# whoop-v0_11td.net
KiCad netlist of a schematic drawn in EAGLE
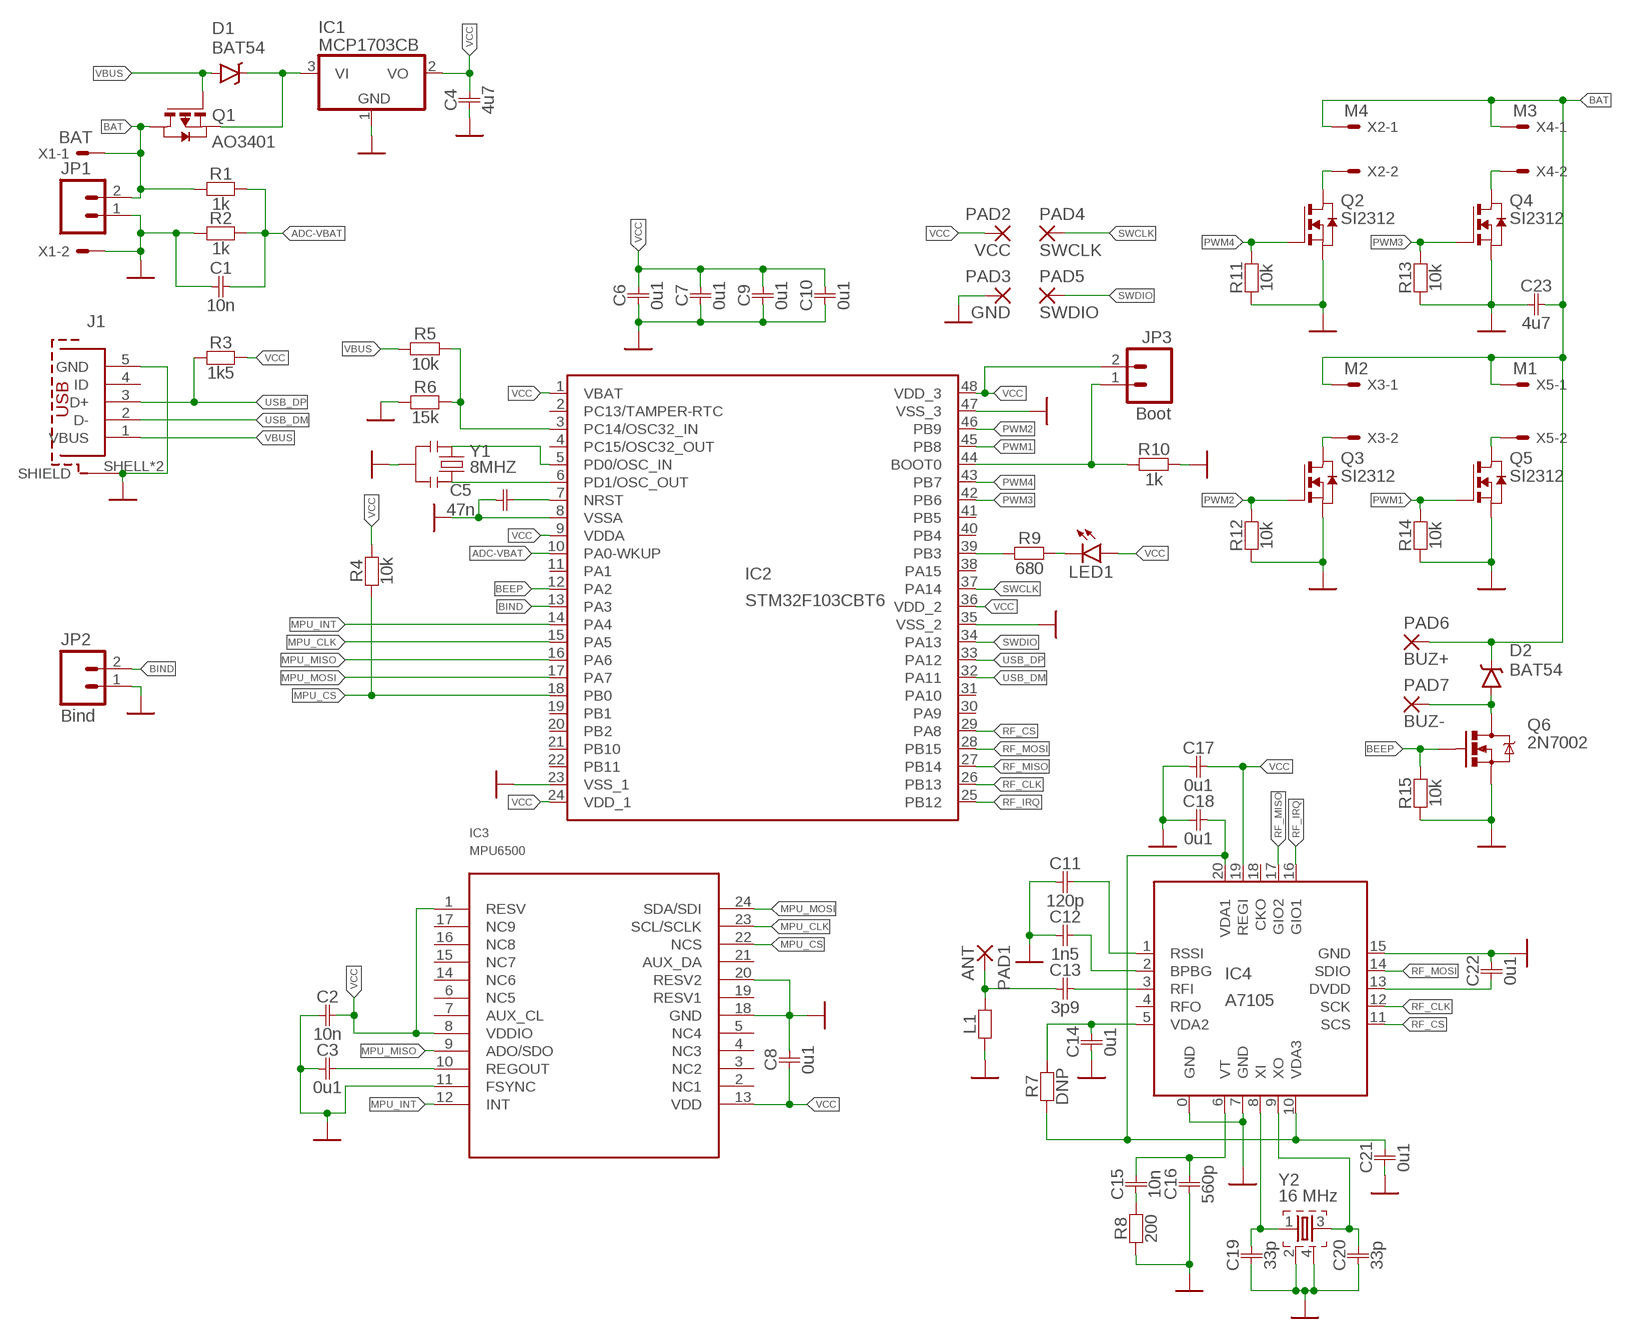
[diagram p0: schematic, sheet 1]

(export (version "E")
  (design (tool "Eeschema 10.0.6"))
  (components
    (comp (ref "C1")
      (value "10n")
      (footprint "eagle-import:0402")
      (libsource (lib "eagle-import") (part "C0402"))
    )
    (comp (ref "C2")
      (value "10n")
      (footprint "eagle-import:0402")
      (libsource (lib "eagle-import") (part "C0402"))
    )
    (comp (ref "C3")
      (value "0u1")
      (footprint "eagle-import:0402")
      (libsource (lib "eagle-import") (part "C0402"))
    )
    (comp (ref "C4")
      (value "4u7")
      (footprint "eagle-import:0805")
      (libsource (lib "eagle-import") (part "C0805"))
    )
    (comp (ref "C5")
      (value "47n")
      (footprint "eagle-import:0402")
      (libsource (lib "eagle-import") (part "C0402"))
    )
    (comp (ref "C6")
      (value "0u1")
      (footprint "eagle-import:0402")
      (libsource (lib "eagle-import") (part "C0402"))
    )
    (comp (ref "C7")
      (value "0u1")
      (footprint "eagle-import:0402")
      (libsource (lib "eagle-import") (part "C0402"))
    )
    (comp (ref "C8")
      (value "0u1")
      (footprint "eagle-import:0402")
      (libsource (lib "eagle-import") (part "C0402"))
    )
    (comp (ref "C9")
      (value "0u1")
      (footprint "eagle-import:0402")
      (libsource (lib "eagle-import") (part "C0402"))
    )
    (comp (ref "C10")
      (value "0u1")
      (footprint "eagle-import:0402")
      (libsource (lib "eagle-import") (part "C0402"))
    )
    (comp (ref "C11")
      (value "120p")
      (footprint "eagle-import:0402")
      (libsource (lib "eagle-import") (part "C0402"))
    )
    (comp (ref "C12")
      (value "1n5")
      (footprint "eagle-import:0402")
      (libsource (lib "eagle-import") (part "C0402"))
    )
    (comp (ref "C13")
      (value "3p9")
      (footprint "eagle-import:0402")
      (libsource (lib "eagle-import") (part "C0402"))
    )
    (comp (ref "C14")
      (value "0u1")
      (footprint "eagle-import:0402")
      (libsource (lib "eagle-import") (part "C0402"))
    )
    (comp (ref "C15")
      (value "10n")
      (footprint "eagle-import:0402")
      (libsource (lib "eagle-import") (part "C0402"))
    )
    (comp (ref "C16")
      (value "560p")
      (footprint "eagle-import:0402")
      (libsource (lib "eagle-import") (part "C0402"))
    )
    (comp (ref "C17")
      (value "0u1")
      (footprint "eagle-import:0402")
      (libsource (lib "eagle-import") (part "C0402"))
    )
    (comp (ref "C18")
      (value "0u1")
      (footprint "eagle-import:0402")
      (libsource (lib "eagle-import") (part "C0402"))
    )
    (comp (ref "C19")
      (value "33p")
      (footprint "eagle-import:0402")
      (libsource (lib "eagle-import") (part "C0402"))
    )
    (comp (ref "C20")
      (value "33p")
      (footprint "eagle-import:0402")
      (libsource (lib "eagle-import") (part "C0402"))
    )
    (comp (ref "C21")
      (value "0u1")
      (footprint "eagle-import:0402")
      (libsource (lib "eagle-import") (part "C0402"))
    )
    (comp (ref "C22")
      (value "0u1")
      (footprint "eagle-import:0402")
      (libsource (lib "eagle-import") (part "C0402"))
    )
    (comp (ref "C23")
      (value "4u7")
      (footprint "eagle-import:0805")
      (libsource (lib "eagle-import") (part "C0805"))
    )
    (comp (ref "D1")
      (value "BAT54")
      (footprint "eagle-import:SOD-323")
      (libsource (lib "eagle-import") (part "BAT20JFILM"))
    )
    (comp (ref "D2")
      (value "BAT54")
      (footprint "eagle-import:SOD-323")
      (libsource (lib "eagle-import") (part "BAT20JFILM"))
    )
    (comp (ref "IC1")
      (value "MCP1703CB")
      (footprint "eagle-import:SOT23")
      (libsource (lib "eagle-import") (part "MCP1703CB"))
    )
    (comp (ref "IC2")
      (value "STM32F103CBT6")
      (footprint "eagle-import:LQFP48")
      (libsource (lib "eagle-import") (part "STM32F103C8"))
    )
    (comp (ref "IC3")
      (value "MPU6500")
      (footprint "eagle-import:LEAD-QFN24")
      (libsource (lib "eagle-import") (part "MPU-9250"))
    )
    (comp (ref "IC4")
      (value "A7105")
      (footprint "eagle-import:QFN20")
      (libsource (lib "eagle-import") (part "A7105"))
    )
    (comp (ref "J1")
      (value "614105150721")
      (footprint "eagle-import:614105150721")
      (libsource (lib "eagle-import") (part "614105150721"))
    )
    (comp (ref "JP1")
      (value "M022MM")
      (footprint "eagle-import:1X02_2MM")
      (libsource (lib "eagle-import") (part "M022MM"))
    )
    (comp (ref "JP2")
      (value "Bind")
      (footprint "eagle-import:1X02_1.27MM")
      (libsource (lib "eagle-import") (part "M021.27MM"))
    )
    (comp (ref "JP3")
      (value "Boot")
      (footprint "eagle-import:1X02_1.27MM")
      (libsource (lib "eagle-import") (part "M021.27MM"))
    )
    (comp (ref "L1")
      (value "R0402")
      (footprint "eagle-import:0402")
      (libsource (lib "eagle-import") (part "R0402"))
    )
    (comp (ref "LED1")
      (value "LED-RED0603")
      (footprint "eagle-import:LED-0603")
      (libsource (lib "eagle-import") (part "LED-RED0603"))
    )
    (comp (ref "PAD1")
      (value "ANT")
      (footprint "eagle-import:1,6_0,8")
      (libsource (lib "eagle-import") (part "1,6/0,8"))
    )
    (comp (ref "PAD2")
      (value "VCC")
      (footprint "eagle-import:SMD1,27-2,54")
      (libsource (lib "eagle-import") (part "SMD2"))
    )
    (comp (ref "PAD3")
      (value "GND")
      (footprint "eagle-import:SMD1,27-2,54")
      (libsource (lib "eagle-import") (part "SMD2"))
    )
    (comp (ref "PAD4")
      (value "SWCLK")
      (footprint "eagle-import:SMD1,27-2,54")
      (libsource (lib "eagle-import") (part "SMD2"))
    )
    (comp (ref "PAD5")
      (value "SWDIO")
      (footprint "eagle-import:SMD1,27-2,54")
      (libsource (lib "eagle-import") (part "SMD2"))
    )
    (comp (ref "PAD6")
      (value "BUZ+")
      (footprint "eagle-import:SMD1,27-2,54")
      (libsource (lib "eagle-import") (part "SMD2"))
    )
    (comp (ref "PAD7")
      (value "BUZ-")
      (footprint "eagle-import:SMD1,27-2,54")
      (libsource (lib "eagle-import") (part "SMD2"))
    )
    (comp (ref "Q1")
      (value "AO3401")
      (footprint "eagle-import:SOT-23")
      (libsource (lib "eagle-import") (part "PMOSSOT23"))
    )
    (comp (ref "Q2")
      (value "SI2312")
      (footprint "eagle-import:SOT-23")
      (libsource (lib "eagle-import") (part "NMOSSOT23"))
    )
    (comp (ref "Q3")
      (value "SI2312")
      (footprint "eagle-import:SOT-23")
      (libsource (lib "eagle-import") (part "NMOSSOT23"))
    )
    (comp (ref "Q4")
      (value "SI2312")
      (footprint "eagle-import:SOT-23")
      (libsource (lib "eagle-import") (part "NMOSSOT23"))
    )
    (comp (ref "Q5")
      (value "SI2312")
      (footprint "eagle-import:SOT-23")
      (libsource (lib "eagle-import") (part "NMOSSOT23"))
    )
    (comp (ref "Q6")
      (value "2N7002")
      (footprint "eagle-import:SOT323")
      (libsource (lib "eagle-import") (part "MOSFET-NCHANNEL2N7002PW"))
    )
    (comp (ref "R1")
      (value "1k")
      (footprint "eagle-import:0402")
      (libsource (lib "eagle-import") (part "R0402"))
    )
    (comp (ref "R2")
      (value "1k")
      (footprint "eagle-import:0402")
      (libsource (lib "eagle-import") (part "R0402"))
    )
    (comp (ref "R3")
      (value "1k5")
      (footprint "eagle-import:0402")
      (libsource (lib "eagle-import") (part "R0402"))
    )
    (comp (ref "R4")
      (value "10k")
      (footprint "eagle-import:0402")
      (libsource (lib "eagle-import") (part "R0402"))
    )
    (comp (ref "R5")
      (value "10k")
      (footprint "eagle-import:0402")
      (libsource (lib "eagle-import") (part "R0402"))
    )
    (comp (ref "R6")
      (value "15k")
      (footprint "eagle-import:0402")
      (libsource (lib "eagle-import") (part "R0402"))
    )
    (comp (ref "R7")
      (value "DNP")
      (footprint "eagle-import:0402")
      (libsource (lib "eagle-import") (part "R0402"))
    )
    (comp (ref "R8")
      (value "200")
      (footprint "eagle-import:0402")
      (libsource (lib "eagle-import") (part "R0402"))
    )
    (comp (ref "R9")
      (value "680")
      (footprint "eagle-import:0402")
      (libsource (lib "eagle-import") (part "R0402"))
    )
    (comp (ref "R10")
      (value "1k")
      (footprint "eagle-import:0402")
      (libsource (lib "eagle-import") (part "R0402"))
    )
    (comp (ref "R11")
      (value "10k")
      (footprint "eagle-import:0402")
      (libsource (lib "eagle-import") (part "R0402"))
    )
    (comp (ref "R12")
      (value "10k")
      (footprint "eagle-import:0402")
      (libsource (lib "eagle-import") (part "R0402"))
    )
    (comp (ref "R13")
      (value "10k")
      (footprint "eagle-import:0402")
      (libsource (lib "eagle-import") (part "R0402"))
    )
    (comp (ref "R14")
      (value "10k")
      (footprint "eagle-import:0402")
      (libsource (lib "eagle-import") (part "R0402"))
    )
    (comp (ref "R15")
      (value "10k")
      (footprint "eagle-import:0402")
      (libsource (lib "eagle-import") (part "R0402"))
    )
    (comp (ref "X1")
      (value "BAT")
      (footprint "eagle-import:53047-02")
      (fields (field (name "MF") "MOLEX") (field (name "MPN") "53047-0210"))
      (libsource (lib "eagle-import") (part "53?-02047"))
    )
    (comp (ref "X2")
      (value "M4")
      (footprint "eagle-import:53047-02")
      (fields (field (name "MF") "MOLEX") (field (name "MPN") "53047-0210"))
      (libsource (lib "eagle-import") (part "53?-02047"))
    )
    (comp (ref "X3")
      (value "M2")
      (footprint "eagle-import:53047-02")
      (fields (field (name "MF") "MOLEX") (field (name "MPN") "53047-0210"))
      (libsource (lib "eagle-import") (part "53?-02047"))
    )
    (comp (ref "X4")
      (value "M3")
      (footprint "eagle-import:53047-02")
      (fields (field (name "MF") "MOLEX") (field (name "MPN") "53047-0210"))
      (libsource (lib "eagle-import") (part "53?-02047"))
    )
    (comp (ref "X5")
      (value "M1")
      (footprint "eagle-import:53047-02")
      (fields (field (name "MF") "MOLEX") (field (name "MPN") "53047-0210"))
      (libsource (lib "eagle-import") (part "53?-02047"))
    )
    (comp (ref "Y1")
      (value "8MHZ")
      (footprint "eagle-import:RESONATOR-SMD")
      (libsource (lib "eagle-import") (part "RESONATOR8MHZ"))
    )
    (comp (ref "Y2")
      (value "16 MHz")
      (footprint "eagle-import:FA-20H")
      (libsource (lib "eagle-import") (part "FA-3225"))
    )
  )
  (nets
    (net (code "1") (name "ADC-VBAT") (class "Default")
      (node (ref "C1") (pin "P$2") (pinfunction "P$2_P$2") (pintype "passive"))
      (node (ref "IC2") (pin "10") (pinfunction "PA0-WKUP_10") (pintype "bidirectional"))
      (node (ref "R1") (pin "P$1") (pinfunction "P$1_P$1") (pintype "passive"))
      (node (ref "R2") (pin "P$1") (pinfunction "P$1_P$1") (pintype "passive"))
    )
    (net (code "2") (name "BAT") (class "Default")
      (node (ref "C23") (pin "P$2") (pinfunction "P$2_P$2") (pintype "passive"))
      (node (ref "D2") (pin "C") (pinfunction "C_C") (pintype "passive"))
      (node (ref "JP1") (pin "2") (pinfunction "2_2") (pintype "passive"))
      (node (ref "PAD6") (pin "1") (pinfunction "P_1") (pintype "passive"))
      (node (ref "Q1") (pin "1") (pinfunction "D_1") (pintype "passive"))
      (node (ref "R1") (pin "P$2") (pinfunction "P$2_P$2") (pintype "passive"))
      (node (ref "X1") (pin "1") (pinfunction "S_1") (pintype "passive"))
      (node (ref "X2") (pin "1") (pinfunction "S_1") (pintype "passive"))
      (node (ref "X3") (pin "1") (pinfunction "S_1") (pintype "passive"))
      (node (ref "X4") (pin "1") (pinfunction "S_1") (pintype "passive"))
      (node (ref "X5") (pin "1") (pinfunction "S_1") (pintype "passive"))
    )
    (net (code "3") (name "BEEP") (class "Default")
      (node (ref "IC2") (pin "12") (pinfunction "PA2_12") (pintype "bidirectional"))
      (node (ref "Q6") (pin "1") (pinfunction "G_1") (pintype "passive"))
      (node (ref "R15") (pin "P$2") (pinfunction "P$2_P$2") (pintype "passive"))
    )
    (net (code "4") (name "BIND") (class "Default")
      (node (ref "IC2") (pin "13") (pinfunction "PA3_13") (pintype "bidirectional"))
      (node (ref "JP2") (pin "2") (pinfunction "2_2") (pintype "passive"))
    )
    (net (code "5") (name "GND") (class "Default")
      (node (ref "C1") (pin "P$1") (pinfunction "P$1_P$1") (pintype "passive"))
      (node (ref "C10") (pin "P$1") (pinfunction "P$1_P$1") (pintype "passive"))
      (node (ref "C11") (pin "P$1") (pinfunction "P$1_P$1") (pintype "passive"))
      (node (ref "C12") (pin "P$1") (pinfunction "P$1_P$1") (pintype "passive"))
      (node (ref "C14") (pin "P$1") (pinfunction "P$1_P$1") (pintype "passive"))
      (node (ref "C16") (pin "P$1") (pinfunction "P$1_P$1") (pintype "passive"))
      (node (ref "C17") (pin "P$1") (pinfunction "P$1_P$1") (pintype "passive"))
      (node (ref "C18") (pin "P$1") (pinfunction "P$1_P$1") (pintype "passive"))
      (node (ref "C19") (pin "P$1") (pinfunction "P$1_P$1") (pintype "passive"))
      (node (ref "C2") (pin "P$1") (pinfunction "P$1_P$1") (pintype "passive"))
      (node (ref "C20") (pin "P$1") (pinfunction "P$1_P$1") (pintype "passive"))
      (node (ref "C21") (pin "P$1") (pinfunction "P$1_P$1") (pintype "passive"))
      (node (ref "C22") (pin "P$2") (pinfunction "P$2_P$2") (pintype "passive"))
      (node (ref "C23") (pin "P$1") (pinfunction "P$1_P$1") (pintype "passive"))
      (node (ref "C3") (pin "P$1") (pinfunction "P$1_P$1") (pintype "passive"))
      (node (ref "C4") (pin "P$1") (pinfunction "P$1_P$1") (pintype "passive"))
      (node (ref "C5") (pin "P$1") (pinfunction "P$1_P$1") (pintype "passive"))
      (node (ref "C6") (pin "P$1") (pinfunction "P$1_P$1") (pintype "passive"))
      (node (ref "C7") (pin "P$1") (pinfunction "P$1_P$1") (pintype "passive"))
      (node (ref "C8") (pin "P$2") (pinfunction "P$2_P$2") (pintype "passive"))
      (node (ref "C9") (pin "P$1") (pinfunction "P$1_P$1") (pintype "passive"))
      (node (ref "IC1") (pin "1") (pinfunction "GND_1") (pintype "passive"))
      (node (ref "IC2") (pin "23") (pinfunction "VSS_1_23") (pintype "power_in"))
      (node (ref "IC2") (pin "35") (pinfunction "VSS_2_35") (pintype "power_in"))
      (node (ref "IC2") (pin "47") (pinfunction "VSS_3_47") (pintype "power_in"))
      (node (ref "IC2") (pin "8") (pinfunction "VSSA_8") (pintype "power_in"))
      (node (ref "IC3") (pin "11") (pinfunction "FSYNC_11") (pintype "bidirectional"))
      (node (ref "IC3") (pin "18") (pinfunction "GND_18") (pintype "bidirectional"))
      (node (ref "IC3") (pin "20") (pinfunction "RESV2_20") (pintype "bidirectional"))
      (node (ref "IC4") (pin "0") (pinfunction "GND_0") (pintype "power_in"))
      (node (ref "IC4") (pin "15") (pinfunction "GND_15") (pintype "power_in"))
      (node (ref "IC4") (pin "7") (pinfunction "GND_7") (pintype "power_in"))
      (node (ref "J1") (pin "5") (pinfunction "GND_5") (pintype "passive"))
      (node (ref "J1") (pin "SHELL") (pinfunction "SHIELD_SHELL") (pintype "passive"))
      (node (ref "J1") (pin "SHELL1") (pinfunction "SHIELD_SHELL1") (pintype "passive"))
      (node (ref "JP1") (pin "1") (pinfunction "1_1") (pintype "passive"))
      (node (ref "JP2") (pin "1") (pinfunction "1_1") (pintype "passive"))
      (node (ref "L1") (pin "P$1") (pinfunction "P$1_P$1") (pintype "passive"))
      (node (ref "PAD3") (pin "1") (pinfunction "P_1") (pintype "passive"))
      (node (ref "Q2") (pin "2") (pinfunction "S_2") (pintype "passive"))
      (node (ref "Q3") (pin "2") (pinfunction "S_2") (pintype "passive"))
      (node (ref "Q4") (pin "2") (pinfunction "S_2") (pintype "passive"))
      (node (ref "Q5") (pin "2") (pinfunction "S_2") (pintype "passive"))
      (node (ref "Q6") (pin "2") (pinfunction "S_2") (pintype "passive"))
      (node (ref "R10") (pin "P$2") (pinfunction "P$2_P$2") (pintype "passive"))
      (node (ref "R11") (pin "P$1") (pinfunction "P$1_P$1") (pintype "passive"))
      (node (ref "R12") (pin "P$1") (pinfunction "P$1_P$1") (pintype "passive"))
      (node (ref "R13") (pin "P$1") (pinfunction "P$1_P$1") (pintype "passive"))
      (node (ref "R14") (pin "P$1") (pinfunction "P$1_P$1") (pintype "passive"))
      (node (ref "R15") (pin "P$1") (pinfunction "P$1_P$1") (pintype "passive"))
      (node (ref "R2") (pin "P$2") (pinfunction "P$2_P$2") (pintype "passive"))
      (node (ref "R6") (pin "P$2") (pinfunction "P$2_P$2") (pintype "passive"))
      (node (ref "R8") (pin "P$1") (pinfunction "P$1_P$1") (pintype "passive"))
      (node (ref "X1") (pin "2") (pinfunction "S_2") (pintype "passive"))
      (node (ref "Y1") (pin "2") (pinfunction "2_2") (pintype "passive"))
      (node (ref "Y2") (pin "2") (pinfunction "2_2") (pintype "passive"))
      (node (ref "Y2") (pin "4") (pinfunction "4_4") (pintype "passive"))
    )
    (net (code "6") (name "MPU_CLK") (class "Default")
      (node (ref "IC2") (pin "15") (pinfunction "PA5_15") (pintype "bidirectional"))
      (node (ref "IC3") (pin "23") (pinfunction "SCL/SCLK_23") (pintype "bidirectional"))
    )
    (net (code "7") (name "MPU_CS") (class "Default")
      (node (ref "IC2") (pin "18") (pinfunction "PB0_18") (pintype "bidirectional"))
      (node (ref "IC3") (pin "22") (pinfunction "NCS_22") (pintype "bidirectional"))
      (node (ref "R4") (pin "P$1") (pinfunction "P$1_P$1") (pintype "passive"))
    )
    (net (code "8") (name "MPU_INT") (class "Default")
      (node (ref "IC2") (pin "14") (pinfunction "PA4_14") (pintype "bidirectional"))
      (node (ref "IC3") (pin "12") (pinfunction "INT_12") (pintype "bidirectional"))
    )
    (net (code "9") (name "MPU_MISO") (class "Default")
      (node (ref "IC2") (pin "16") (pinfunction "PA6_16") (pintype "bidirectional"))
      (node (ref "IC3") (pin "9") (pinfunction "ADO/SDO_9") (pintype "bidirectional"))
    )
    (net (code "10") (name "MPU_MOSI") (class "Default")
      (node (ref "IC2") (pin "17") (pinfunction "PA7_17") (pintype "bidirectional"))
      (node (ref "IC3") (pin "24") (pinfunction "SDA/SDI_24") (pintype "bidirectional"))
    )
    (net (code "11") (name "Net-(C15-PadP$1)") (class "Default")
      (node (ref "C15") (pin "P$1") (pinfunction "P$1_P$1") (pintype "passive"))
      (node (ref "R8") (pin "P$2") (pinfunction "P$2_P$2") (pintype "passive"))
    )
    (net (code "12") (name "Net-(IC1-VI)") (class "Default")
      (node (ref "D1") (pin "C") (pinfunction "C_C") (pintype "passive"))
      (node (ref "IC1") (pin "3") (pinfunction "VI_3") (pintype "input"))
      (node (ref "Q1") (pin "2") (pinfunction "S_2") (pintype "passive"))
    )
    (net (code "13") (name "Net-(IC2-BOOT0)") (class "Default")
      (node (ref "IC2") (pin "44") (pinfunction "BOOT0_44") (pintype "input"))
      (node (ref "JP3") (pin "1") (pinfunction "1_1") (pintype "passive"))
      (node (ref "R10") (pin "P$1") (pinfunction "P$1_P$1") (pintype "passive"))
    )
    (net (code "14") (name "Net-(IC2-NRST)") (class "Default")
      (node (ref "C5") (pin "P$2") (pinfunction "P$2_P$2") (pintype "passive"))
      (node (ref "IC2") (pin "7") (pinfunction "NRST_7") (pintype "input"))
    )
    (net (code "15") (name "Net-(IC2-PB3)") (class "Default")
      (node (ref "IC2") (pin "39") (pinfunction "PB3_39") (pintype "bidirectional"))
      (node (ref "R9") (pin "P$1") (pinfunction "P$1_P$1") (pintype "passive"))
    )
    (net (code "16") (name "Net-(IC2-PC14{slash}OSC32_IN)") (class "Default")
      (node (ref "IC2") (pin "3") (pinfunction "PC14/OSC32_IN_3") (pintype "bidirectional"))
      (node (ref "R5") (pin "P$2") (pinfunction "P$2_P$2") (pintype "passive"))
      (node (ref "R6") (pin "P$1") (pinfunction "P$1_P$1") (pintype "passive"))
    )
    (net (code "17") (name "Net-(IC2-PD0{slash}OSC_IN)") (class "Default")
      (node (ref "IC2") (pin "5") (pinfunction "PD0/OSC_IN_5") (pintype "bidirectional"))
      (node (ref "Y1") (pin "1") (pinfunction "1_1") (pintype "passive"))
    )
    (net (code "18") (name "Net-(IC2-PD1{slash}OSC_OUT)") (class "Default")
      (node (ref "IC2") (pin "6") (pinfunction "PD1/OSC_OUT_6") (pintype "bidirectional"))
      (node (ref "Y1") (pin "3") (pinfunction "3_3") (pintype "passive"))
    )
    (net (code "19") (name "Net-(IC3-REGOUT)") (class "Default")
      (node (ref "C3") (pin "P$2") (pinfunction "P$2_P$2") (pintype "passive"))
      (node (ref "IC3") (pin "10") (pinfunction "REGOUT_10") (pintype "bidirectional"))
    )
    (net (code "20") (name "Net-(IC4-BPBG)") (class "Default")
      (node (ref "C12") (pin "P$2") (pinfunction "P$2_P$2") (pintype "passive"))
      (node (ref "IC4") (pin "2") (pinfunction "BPBG_2") (pintype "output"))
    )
    (net (code "21") (name "Net-(IC4-DVDD)") (class "Default")
      (node (ref "C22") (pin "P$1") (pinfunction "P$1_P$1") (pintype "passive"))
      (node (ref "IC4") (pin "13") (pinfunction "DVDD_13") (pintype "input"))
    )
    (net (code "22") (name "Net-(IC4-RFI)") (class "Default")
      (node (ref "C13") (pin "P$2") (pinfunction "P$2_P$2") (pintype "passive"))
      (node (ref "IC4") (pin "3") (pinfunction "RFI_3") (pintype "input"))
    )
    (net (code "23") (name "Net-(IC4-RSSI)") (class "Default")
      (node (ref "C11") (pin "P$2") (pinfunction "P$2_P$2") (pintype "passive"))
      (node (ref "IC4") (pin "1") (pinfunction "RSSI_1") (pintype "output"))
    )
    (net (code "24") (name "Net-(IC4-VDA1)") (class "Default")
      (node (ref "C18") (pin "P$2") (pinfunction "P$2_P$2") (pintype "passive"))
      (node (ref "C21") (pin "P$2") (pinfunction "P$2_P$2") (pintype "passive"))
      (node (ref "IC4") (pin "10") (pinfunction "VDA3_10") (pintype "input"))
      (node (ref "IC4") (pin "20") (pinfunction "VDA1_20") (pintype "bidirectional"))
      (node (ref "R7") (pin "P$1") (pinfunction "P$1_P$1") (pintype "passive"))
    )
    (net (code "25") (name "Net-(IC4-VDA2)") (class "Default")
      (node (ref "C14") (pin "P$2") (pinfunction "P$2_P$2") (pintype "passive"))
      (node (ref "IC4") (pin "5") (pinfunction "VDA2_5") (pintype "bidirectional"))
      (node (ref "R7") (pin "P$2") (pinfunction "P$2_P$2") (pintype "passive"))
    )
    (net (code "26") (name "Net-(IC4-VT)") (class "Default")
      (node (ref "C15") (pin "P$2") (pinfunction "P$2_P$2") (pintype "passive"))
      (node (ref "C16") (pin "P$2") (pinfunction "P$2_P$2") (pintype "passive"))
      (node (ref "IC4") (pin "6") (pinfunction "VT_6") (pintype "input"))
    )
    (net (code "27") (name "Net-(IC4-XI)") (class "Default")
      (node (ref "C19") (pin "P$2") (pinfunction "P$2_P$2") (pintype "passive"))
      (node (ref "IC4") (pin "8") (pinfunction "XI_8") (pintype "input"))
      (node (ref "Y2") (pin "1") (pinfunction "1_1") (pintype "passive"))
    )
    (net (code "28") (name "Net-(IC4-XO)") (class "Default")
      (node (ref "C20") (pin "P$2") (pinfunction "P$2_P$2") (pintype "passive"))
      (node (ref "IC4") (pin "9") (pinfunction "XO_9") (pintype "output"))
      (node (ref "Y2") (pin "3") (pinfunction "3_3") (pintype "passive"))
    )
    (net (code "29") (name "Net-(LED1-PadC)") (class "Default")
      (node (ref "LED1") (pin "C") (pinfunction "C_C") (pintype "passive"))
      (node (ref "R9") (pin "P$2") (pinfunction "P$2_P$2") (pintype "passive"))
    )
    (net (code "30") (name "Net-(PAD1-P)") (class "Default")
      (node (ref "C13") (pin "P$1") (pinfunction "P$1_P$1") (pintype "passive"))
      (node (ref "L1") (pin "P$2") (pinfunction "P$2_P$2") (pintype "passive"))
      (node (ref "PAD1") (pin "1") (pinfunction "P_1") (pintype "passive"))
    )
    (net (code "31") (name "Net-(PAD7-P)") (class "Default")
      (node (ref "D2") (pin "A") (pinfunction "A_A") (pintype "passive"))
      (node (ref "PAD7") (pin "1") (pinfunction "P_1") (pintype "passive"))
      (node (ref "Q6") (pin "3") (pinfunction "D_3") (pintype "passive"))
    )
    (net (code "32") (name "Net-(Q2-D)") (class "Default")
      (node (ref "Q2") (pin "1") (pinfunction "D_1") (pintype "passive"))
      (node (ref "X2") (pin "2") (pinfunction "S_2") (pintype "passive"))
    )
    (net (code "33") (name "Net-(Q3-D)") (class "Default")
      (node (ref "Q3") (pin "1") (pinfunction "D_1") (pintype "passive"))
      (node (ref "X3") (pin "2") (pinfunction "S_2") (pintype "passive"))
    )
    (net (code "34") (name "Net-(Q4-D)") (class "Default")
      (node (ref "Q4") (pin "1") (pinfunction "D_1") (pintype "passive"))
      (node (ref "X4") (pin "2") (pinfunction "S_2") (pintype "passive"))
    )
    (net (code "35") (name "Net-(Q5-D)") (class "Default")
      (node (ref "Q5") (pin "1") (pinfunction "D_1") (pintype "passive"))
      (node (ref "X5") (pin "2") (pinfunction "S_2") (pintype "passive"))
    )
    (net (code "36") (name "PWM1") (class "Default")
      (node (ref "IC2") (pin "45") (pinfunction "PB8_45") (pintype "bidirectional"))
      (node (ref "Q5") (pin "3") (pinfunction "G_3") (pintype "passive"))
      (node (ref "R14") (pin "P$2") (pinfunction "P$2_P$2") (pintype "passive"))
    )
    (net (code "37") (name "PWM2") (class "Default")
      (node (ref "IC2") (pin "46") (pinfunction "PB9_46") (pintype "bidirectional"))
      (node (ref "Q3") (pin "3") (pinfunction "G_3") (pintype "passive"))
      (node (ref "R12") (pin "P$2") (pinfunction "P$2_P$2") (pintype "passive"))
    )
    (net (code "38") (name "PWM3") (class "Default")
      (node (ref "IC2") (pin "42") (pinfunction "PB6_42") (pintype "bidirectional"))
      (node (ref "Q4") (pin "3") (pinfunction "G_3") (pintype "passive"))
      (node (ref "R13") (pin "P$2") (pinfunction "P$2_P$2") (pintype "passive"))
    )
    (net (code "39") (name "PWM4") (class "Default")
      (node (ref "IC2") (pin "43") (pinfunction "PB7_43") (pintype "bidirectional"))
      (node (ref "Q2") (pin "3") (pinfunction "G_3") (pintype "passive"))
      (node (ref "R11") (pin "P$2") (pinfunction "P$2_P$2") (pintype "passive"))
    )
    (net (code "40") (name "RF_CLK") (class "Default")
      (node (ref "IC2") (pin "26") (pinfunction "PB13_26") (pintype "bidirectional"))
      (node (ref "IC4") (pin "12") (pinfunction "SCK_12") (pintype "input"))
    )
    (net (code "41") (name "RF_CS") (class "Default")
      (node (ref "IC2") (pin "29") (pinfunction "PA8_29") (pintype "bidirectional"))
      (node (ref "IC4") (pin "11") (pinfunction "SCS_11") (pintype "input"))
    )
    (net (code "42") (name "RF_IRQ") (class "Default")
      (node (ref "IC2") (pin "25") (pinfunction "PB12_25") (pintype "bidirectional"))
      (node (ref "IC4") (pin "16") (pinfunction "GIO1_16") (pintype "bidirectional"))
    )
    (net (code "43") (name "RF_MISO") (class "Default")
      (node (ref "IC2") (pin "27") (pinfunction "PB14_27") (pintype "bidirectional"))
      (node (ref "IC4") (pin "17") (pinfunction "GIO2_17") (pintype "bidirectional"))
    )
    (net (code "44") (name "RF_MOSI") (class "Default")
      (node (ref "IC2") (pin "28") (pinfunction "PB15_28") (pintype "bidirectional"))
      (node (ref "IC4") (pin "14") (pinfunction "SDIO_14") (pintype "bidirectional"))
    )
    (net (code "45") (name "SWCLK") (class "Default")
      (node (ref "IC2") (pin "37") (pinfunction "PA14_37") (pintype "bidirectional"))
      (node (ref "PAD4") (pin "1") (pinfunction "P_1") (pintype "passive"))
    )
    (net (code "46") (name "SWDIO") (class "Default")
      (node (ref "IC2") (pin "34") (pinfunction "PA13_34") (pintype "bidirectional"))
      (node (ref "PAD5") (pin "1") (pinfunction "P_1") (pintype "passive"))
    )
    (net (code "47") (name "USB_DM") (class "Default")
      (node (ref "IC2") (pin "32") (pinfunction "PA11_32") (pintype "bidirectional"))
      (node (ref "J1") (pin "2") (pinfunction "D-_2") (pintype "passive"))
    )
    (net (code "48") (name "USB_DP") (class "Default")
      (node (ref "IC2") (pin "33") (pinfunction "PA12_33") (pintype "bidirectional"))
      (node (ref "J1") (pin "3") (pinfunction "D+_3") (pintype "passive"))
      (node (ref "R3") (pin "P$2") (pinfunction "P$2_P$2") (pintype "passive"))
    )
    (net (code "49") (name "VBUS") (class "Default")
      (node (ref "D1") (pin "A") (pinfunction "A_A") (pintype "passive"))
      (node (ref "J1") (pin "1") (pinfunction "VBUS_1") (pintype "passive"))
      (node (ref "Q1") (pin "3") (pinfunction "G_3") (pintype "passive"))
      (node (ref "R5") (pin "P$1") (pinfunction "P$1_P$1") (pintype "passive"))
    )
    (net (code "50") (name "VCC") (class "Default")
      (node (ref "C10") (pin "P$2") (pinfunction "P$2_P$2") (pintype "passive"))
      (node (ref "C17") (pin "P$2") (pinfunction "P$2_P$2") (pintype "passive"))
      (node (ref "C2") (pin "P$2") (pinfunction "P$2_P$2") (pintype "passive"))
      (node (ref "C4") (pin "P$2") (pinfunction "P$2_P$2") (pintype "passive"))
      (node (ref "C6") (pin "P$2") (pinfunction "P$2_P$2") (pintype "passive"))
      (node (ref "C7") (pin "P$2") (pinfunction "P$2_P$2") (pintype "passive"))
      (node (ref "C8") (pin "P$1") (pinfunction "P$1_P$1") (pintype "passive"))
      (node (ref "C9") (pin "P$2") (pinfunction "P$2_P$2") (pintype "passive"))
      (node (ref "IC1") (pin "2") (pinfunction "VO_2") (pintype "passive"))
      (node (ref "IC2") (pin "1") (pinfunction "VBAT_1") (pintype "power_in"))
      (node (ref "IC2") (pin "24") (pinfunction "VDD_1_24") (pintype "power_in"))
      (node (ref "IC2") (pin "36") (pinfunction "VDD_2_36") (pintype "power_in"))
      (node (ref "IC2") (pin "48") (pinfunction "VDD_3_48") (pintype "power_in"))
      (node (ref "IC2") (pin "9") (pinfunction "VDDA_9") (pintype "power_in"))
      (node (ref "IC3") (pin "1") (pinfunction "RESV_1") (pintype "bidirectional"))
      (node (ref "IC3") (pin "13") (pinfunction "VDD_13") (pintype "bidirectional"))
      (node (ref "IC3") (pin "8") (pinfunction "VDDIO_8") (pintype "bidirectional"))
      (node (ref "IC4") (pin "19") (pinfunction "REGI_19") (pintype "power_in"))
      (node (ref "JP3") (pin "2") (pinfunction "2_2") (pintype "passive"))
      (node (ref "LED1") (pin "A") (pinfunction "A_A") (pintype "passive"))
      (node (ref "PAD2") (pin "1") (pinfunction "P_1") (pintype "passive"))
      (node (ref "R3") (pin "P$1") (pinfunction "P$1_P$1") (pintype "passive"))
      (node (ref "R4") (pin "P$2") (pinfunction "P$2_P$2") (pintype "passive"))
    )
    (net (code "51") (name "unconnected-(IC2-PA1-Pad11)") (class "Default")
      (node (ref "IC2") (pin "11") (pinfunction "PA1_11") (pintype "bidirectional"))
    )
    (net (code "52") (name "unconnected-(IC2-PA9-Pad30)") (class "Default")
      (node (ref "IC2") (pin "30") (pinfunction "PA9_30") (pintype "bidirectional"))
    )
    (net (code "53") (name "unconnected-(IC2-PA10-Pad31)") (class "Default")
      (node (ref "IC2") (pin "31") (pinfunction "PA10_31") (pintype "bidirectional"))
    )
    (net (code "54") (name "unconnected-(IC2-PA15-Pad38)") (class "Default")
      (node (ref "IC2") (pin "38") (pinfunction "PA15_38") (pintype "bidirectional"))
    )
    (net (code "55") (name "unconnected-(IC2-PB1-Pad19)") (class "Default")
      (node (ref "IC2") (pin "19") (pinfunction "PB1_19") (pintype "bidirectional"))
    )
    (net (code "56") (name "unconnected-(IC2-PB2-Pad20)") (class "Default")
      (node (ref "IC2") (pin "20") (pinfunction "PB2_20") (pintype "bidirectional"))
    )
    (net (code "57") (name "unconnected-(IC2-PB4-Pad40)") (class "Default")
      (node (ref "IC2") (pin "40") (pinfunction "PB4_40") (pintype "bidirectional"))
    )
    (net (code "58") (name "unconnected-(IC2-PB5-Pad41)") (class "Default")
      (node (ref "IC2") (pin "41") (pinfunction "PB5_41") (pintype "bidirectional"))
    )
    (net (code "59") (name "unconnected-(IC2-PB10-Pad21)") (class "Default")
      (node (ref "IC2") (pin "21") (pinfunction "PB10_21") (pintype "bidirectional"))
    )
    (net (code "60") (name "unconnected-(IC2-PB11-Pad22)") (class "Default")
      (node (ref "IC2") (pin "22") (pinfunction "PB11_22") (pintype "bidirectional"))
    )
    (net (code "61") (name "unconnected-(IC2-PC13{slash}TAMPER-RTC-Pad2)") (class "Default")
      (node (ref "IC2") (pin "2") (pinfunction "PC13/TAMPER-RTC_2") (pintype "bidirectional"))
    )
    (net (code "62") (name "unconnected-(IC2-PC15{slash}OSC32_OUT-Pad4)") (class "Default")
      (node (ref "IC2") (pin "4") (pinfunction "PC15/OSC32_OUT_4") (pintype "bidirectional"))
    )
    (net (code "63") (name "unconnected-(IC3-AUX_CL-Pad7)") (class "Default")
      (node (ref "IC3") (pin "7") (pinfunction "AUX_CL_7") (pintype "bidirectional"))
    )
    (net (code "64") (name "unconnected-(IC3-AUX_DA-Pad21)") (class "Default")
      (node (ref "IC3") (pin "21") (pinfunction "AUX_DA_21") (pintype "bidirectional"))
    )
    (net (code "65") (name "unconnected-(IC3-NC1-Pad2)") (class "Default")
      (node (ref "IC3") (pin "2") (pinfunction "NC1_2") (pintype "bidirectional"))
    )
    (net (code "66") (name "unconnected-(IC3-NC2-Pad3)") (class "Default")
      (node (ref "IC3") (pin "3") (pinfunction "NC2_3") (pintype "bidirectional"))
    )
    (net (code "67") (name "unconnected-(IC3-NC3-Pad4)") (class "Default")
      (node (ref "IC3") (pin "4") (pinfunction "NC3_4") (pintype "bidirectional"))
    )
    (net (code "68") (name "unconnected-(IC3-NC4-Pad5)") (class "Default")
      (node (ref "IC3") (pin "5") (pinfunction "NC4_5") (pintype "bidirectional"))
    )
    (net (code "69") (name "unconnected-(IC3-NC5-Pad6)") (class "Default")
      (node (ref "IC3") (pin "6") (pinfunction "NC5_6") (pintype "bidirectional"))
    )
    (net (code "70") (name "unconnected-(IC3-NC6-Pad14)") (class "Default")
      (node (ref "IC3") (pin "14") (pinfunction "NC6_14") (pintype "bidirectional"))
    )
    (net (code "71") (name "unconnected-(IC3-NC7-Pad15)") (class "Default")
      (node (ref "IC3") (pin "15") (pinfunction "NC7_15") (pintype "bidirectional"))
    )
    (net (code "72") (name "unconnected-(IC3-NC8-Pad16)") (class "Default")
      (node (ref "IC3") (pin "16") (pinfunction "NC8_16") (pintype "bidirectional"))
    )
    (net (code "73") (name "unconnected-(IC3-NC9-Pad17)") (class "Default")
      (node (ref "IC3") (pin "17") (pinfunction "NC9_17") (pintype "bidirectional"))
    )
    (net (code "74") (name "unconnected-(IC3-RESV1-Pad19)") (class "Default")
      (node (ref "IC3") (pin "19") (pinfunction "RESV1_19") (pintype "bidirectional"))
    )
    (net (code "75") (name "unconnected-(IC4-CKO-Pad18)") (class "Default")
      (node (ref "IC4") (pin "18") (pinfunction "CKO_18") (pintype "output"))
    )
    (net (code "76") (name "unconnected-(IC4-RFO-Pad4)") (class "Default")
      (node (ref "IC4") (pin "4") (pinfunction "RFO_4") (pintype "output"))
    )
    (net (code "77") (name "unconnected-(J1-ID-Pad4)") (class "Default")
      (node (ref "J1") (pin "4") (pinfunction "ID_4") (pintype "passive"))
    )
  )
)
